# LM317_regulator.net
KiCad netlist of a schematic drawn in EAGLE
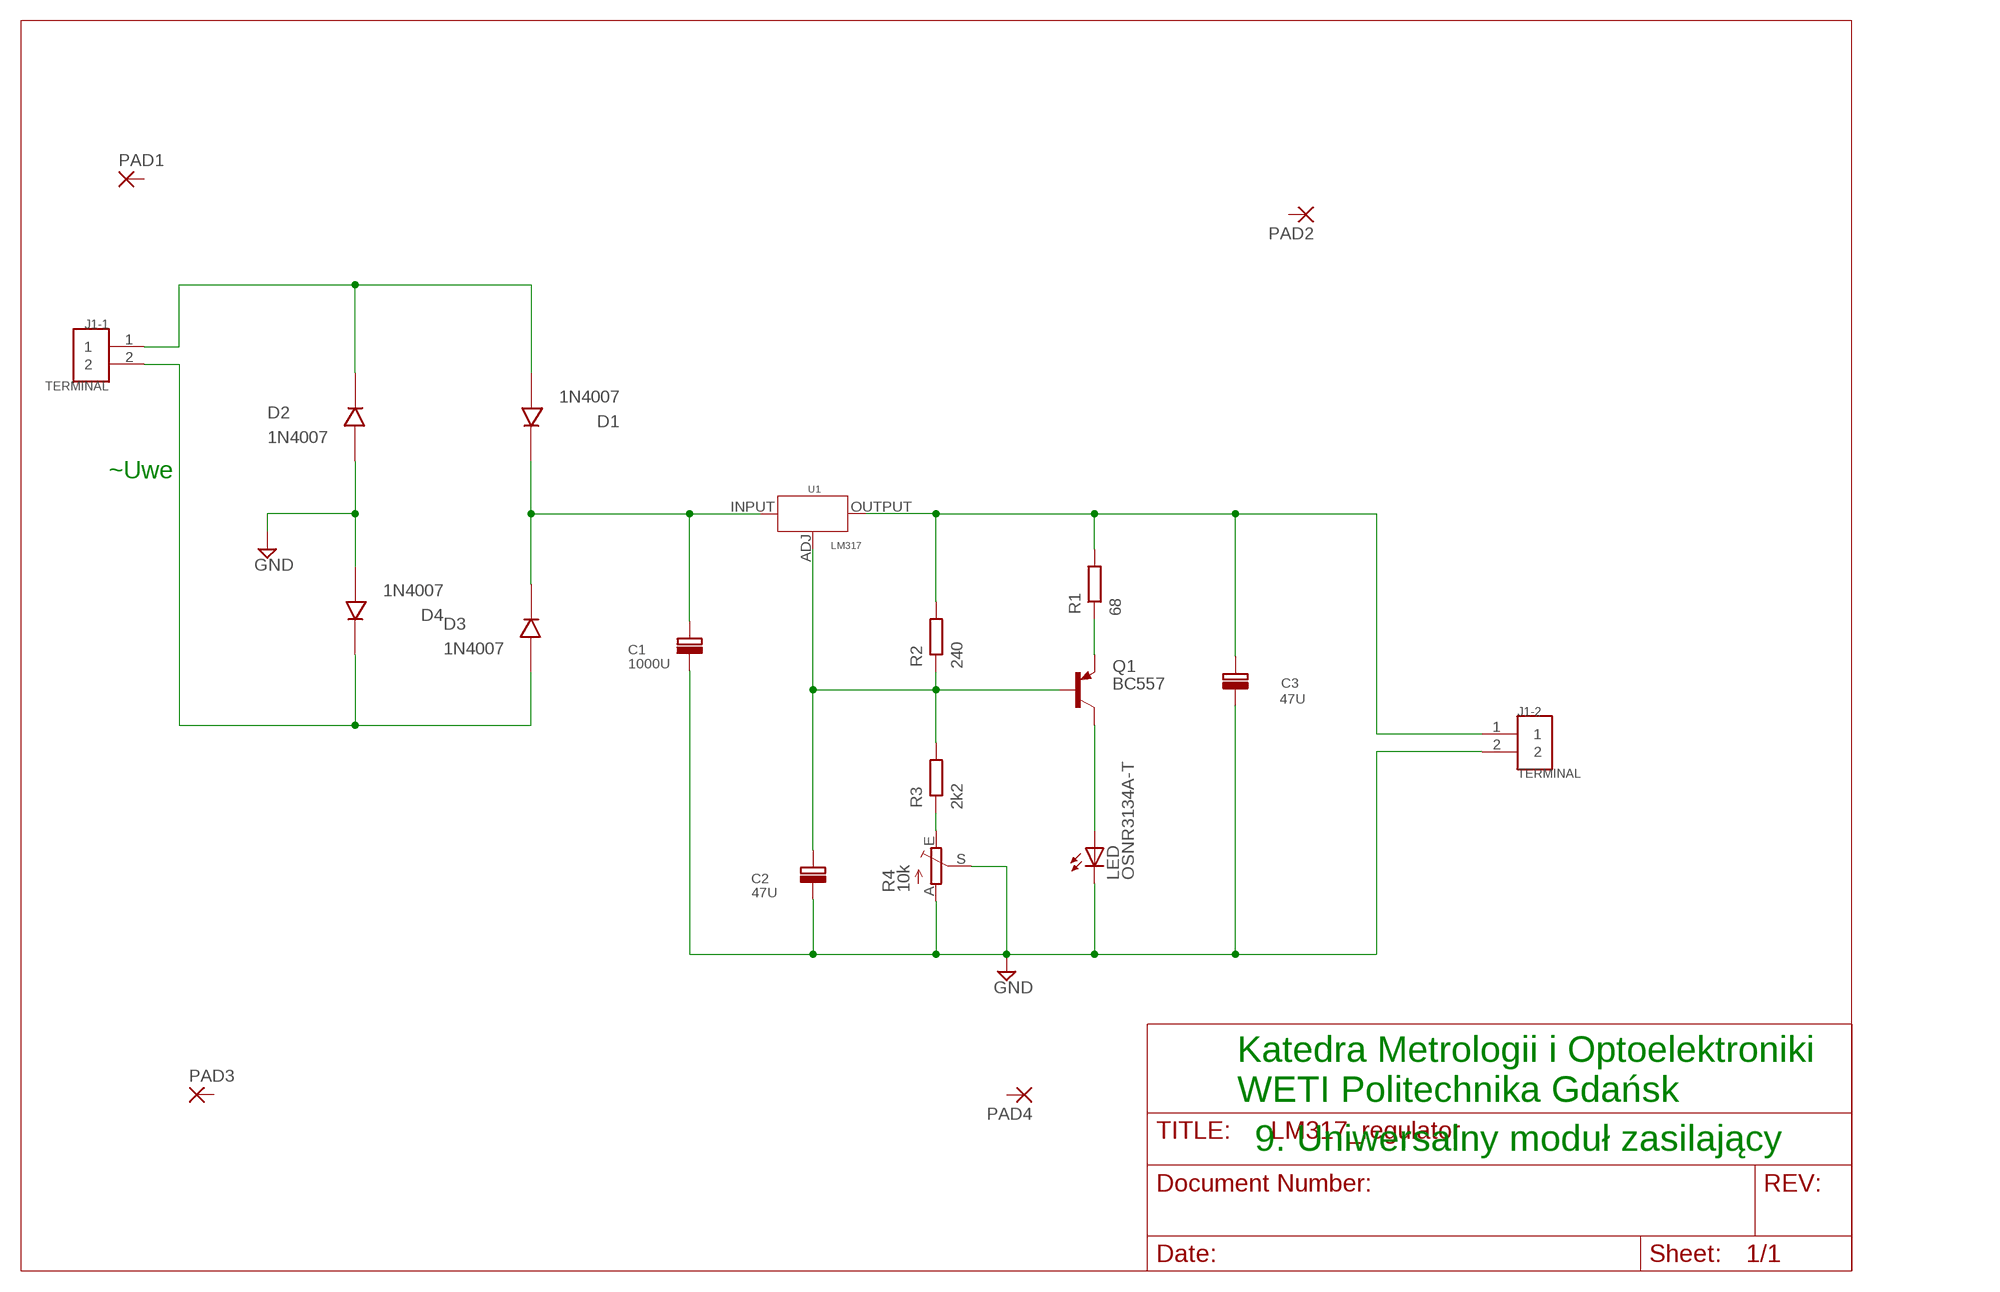
[diagram p0: schematic, sheet 1]

(export (version "E")
  (design (tool "Eeschema 10.0.6"))
  (components
    (comp (ref "C1")
      (value "1000U")
      (footprint "eagle-import:1000U")
      (libsource (lib "eagle-import") (part "1000U"))
    )
    (comp (ref "C2")
      (value "47U")
      (footprint "eagle-import:47U")
      (libsource (lib "eagle-import") (part "47U"))
    )
    (comp (ref "C3")
      (value "47U")
      (footprint "eagle-import:47U")
      (libsource (lib "eagle-import") (part "47U"))
    )
    (comp (ref "D1")
      (value "1N4007")
      (footprint "eagle-import:1N4007")
      (libsource (lib "eagle-import") (part "1N4007"))
    )
    (comp (ref "D2")
      (value "1N4007")
      (footprint "eagle-import:1N4007")
      (libsource (lib "eagle-import") (part "1N4007"))
    )
    (comp (ref "D3")
      (value "1N4007")
      (footprint "eagle-import:1N4007")
      (libsource (lib "eagle-import") (part "1N4007"))
    )
    (comp (ref "D4")
      (value "1N4007")
      (footprint "eagle-import:1N4007")
      (libsource (lib "eagle-import") (part "1N4007"))
    )
    (comp (ref "J1-1")
      (value "TERMINAL")
      (footprint "eagle-import:TERMINAL")
      (libsource (lib "eagle-import") (part "TERMINAL"))
    )
    (comp (ref "J1-2")
      (value "TERMINAL")
      (footprint "eagle-import:TERMINAL")
      (libsource (lib "eagle-import") (part "TERMINAL"))
    )
    (comp (ref "LED")
      (value "OSNR3134A-T")
      (footprint "eagle-import:LED3MM")
      (libsource (lib "eagle-import") (part "LED3MM"))
    )
    (comp (ref "PAD1")
      (value "2,54/1,1")
      (footprint "eagle-import:2,54_1,1")
      (libsource (lib "eagle-import") (part "2,54/1,1"))
    )
    (comp (ref "PAD2")
      (value "2,54/1,1")
      (footprint "eagle-import:2,54_1,1")
      (libsource (lib "eagle-import") (part "2,54/1,1"))
    )
    (comp (ref "PAD3")
      (value "2,54/1,1")
      (footprint "eagle-import:2,54_1,1")
      (libsource (lib "eagle-import") (part "2,54/1,1"))
    )
    (comp (ref "PAD4")
      (value "2,54/1,1")
      (footprint "eagle-import:2,54_1,1")
      (libsource (lib "eagle-import") (part "2,54/1,1"))
    )
    (comp (ref "Q1")
      (value "BC557")
      (footprint "eagle-import:TO92-EBC")
      (libsource (lib "eagle-import") (part "BC557"))
    )
    (comp (ref "R1")
      (value "68")
      (footprint "eagle-import:1206")
      (libsource (lib "eagle-import") (part "1206"))
    )
    (comp (ref "R2")
      (value "240")
      (footprint "eagle-import:1206")
      (libsource (lib "eagle-import") (part "1206"))
    )
    (comp (ref "R3")
      (value "2k2")
      (footprint "eagle-import:1206")
      (libsource (lib "eagle-import") (part "1206"))
    )
    (comp (ref "R4")
      (value "10k")
      (footprint "eagle-import:CA6V")
      (libsource (lib "eagle-import") (part "TRIM_EU-CA6V"))
    )
    (comp (ref "U1")
      (value "LM317")
      (footprint "eagle-import:LM317")
      (libsource (lib "eagle-import") (part "LM317"))
    )
  )
  (nets
    (net (code "1") (name "GND") (class "Default")
      (node (ref "C1") (pin "L") (pinfunction "L_L") (pintype "bidirectional"))
      (node (ref "C2") (pin "L") (pinfunction "L_L") (pintype "bidirectional"))
      (node (ref "C3") (pin "L") (pinfunction "L_L") (pintype "bidirectional"))
      (node (ref "D2") (pin "A") (pinfunction "L_A") (pintype "bidirectional"))
      (node (ref "D4") (pin "A") (pinfunction "L_A") (pintype "bidirectional"))
      (node (ref "J1-2") (pin "2") (pinfunction "2_2") (pintype "passive"))
      (node (ref "LED") (pin "K") (pinfunction "C_K") (pintype "passive"))
      (node (ref "R4") (pin "A") (pinfunction "A_A") (pintype "passive"))
      (node (ref "R4") (pin "S") (pinfunction "S_S") (pintype "passive"))
    )
    (net (code "2") (name "Net-(D1-H)") (class "Default")
      (node (ref "C1") (pin "H") (pinfunction "H_H") (pintype "bidirectional"))
      (node (ref "D1") (pin "C") (pinfunction "H_C") (pintype "bidirectional"))
      (node (ref "D3") (pin "C") (pinfunction "H_C") (pintype "bidirectional"))
      (node (ref "U1") (pin "INPUT") (pinfunction "IN_INPUT") (pintype "bidirectional"))
    )
    (net (code "3") (name "Net-(D1-L)") (class "Default")
      (node (ref "D1") (pin "A") (pinfunction "L_A") (pintype "bidirectional"))
      (node (ref "D2") (pin "C") (pinfunction "H_C") (pintype "bidirectional"))
      (node (ref "J1-1") (pin "1") (pinfunction "1_1") (pintype "passive"))
    )
    (net (code "4") (name "Net-(D3-L)") (class "Default")
      (node (ref "D3") (pin "A") (pinfunction "L_A") (pintype "bidirectional"))
      (node (ref "D4") (pin "C") (pinfunction "H_C") (pintype "bidirectional"))
      (node (ref "J1-1") (pin "2") (pinfunction "2_2") (pintype "passive"))
    )
    (net (code "5") (name "Net-(LED-PadA)") (class "Default")
      (node (ref "LED") (pin "A") (pinfunction "A_A") (pintype "passive"))
      (node (ref "Q1") (pin "C") (pinfunction "C_C") (pintype "passive"))
    )
    (net (code "6") (name "Net-(R1-H)") (class "Default")
      (node (ref "Q1") (pin "E") (pinfunction "E_E") (pintype "passive"))
      (node (ref "R1") (pin "1") (pinfunction "H_1") (pintype "bidirectional"))
    )
    (net (code "7") (name "Net-(R1-L)") (class "Default")
      (node (ref "C3") (pin "H") (pinfunction "H_H") (pintype "bidirectional"))
      (node (ref "J1-2") (pin "1") (pinfunction "1_1") (pintype "passive"))
      (node (ref "R1") (pin "2") (pinfunction "L_2") (pintype "bidirectional"))
      (node (ref "R2") (pin "2") (pinfunction "L_2") (pintype "bidirectional"))
      (node (ref "U1") (pin "OUTPUT") (pinfunction "OUT_OUTPUT") (pintype "bidirectional"))
    )
    (net (code "8") (name "Net-(R2-H)") (class "Default")
      (node (ref "C2") (pin "H") (pinfunction "H_H") (pintype "bidirectional"))
      (node (ref "Q1") (pin "B") (pinfunction "B_B") (pintype "passive"))
      (node (ref "R2") (pin "1") (pinfunction "H_1") (pintype "bidirectional"))
      (node (ref "R3") (pin "2") (pinfunction "L_2") (pintype "bidirectional"))
      (node (ref "U1") (pin "ADJ") (pinfunction "ADJ_ADJ") (pintype "bidirectional"))
    )
    (net (code "9") (name "Net-(R3-H)") (class "Default")
      (node (ref "R3") (pin "1") (pinfunction "H_1") (pintype "bidirectional"))
      (node (ref "R4") (pin "E") (pinfunction "E_E") (pintype "passive"))
    )
    (net (code "10") (name "unconnected-(PAD1-P-Pad1)") (class "Default")
      (node (ref "PAD1") (pin "1") (pinfunction "P_1") (pintype "passive"))
    )
    (net (code "11") (name "unconnected-(PAD2-P-Pad1)") (class "Default")
      (node (ref "PAD2") (pin "1") (pinfunction "P_1") (pintype "passive"))
    )
    (net (code "12") (name "unconnected-(PAD3-P-Pad1)") (class "Default")
      (node (ref "PAD3") (pin "1") (pinfunction "P_1") (pintype "passive"))
    )
    (net (code "13") (name "unconnected-(PAD4-P-Pad1)") (class "Default")
      (node (ref "PAD4") (pin "1") (pinfunction "P_1") (pintype "passive"))
    )
  )
)
